# 08_-_Resolver.net
KiCad netlist of a schematic drawn in Altium Designer
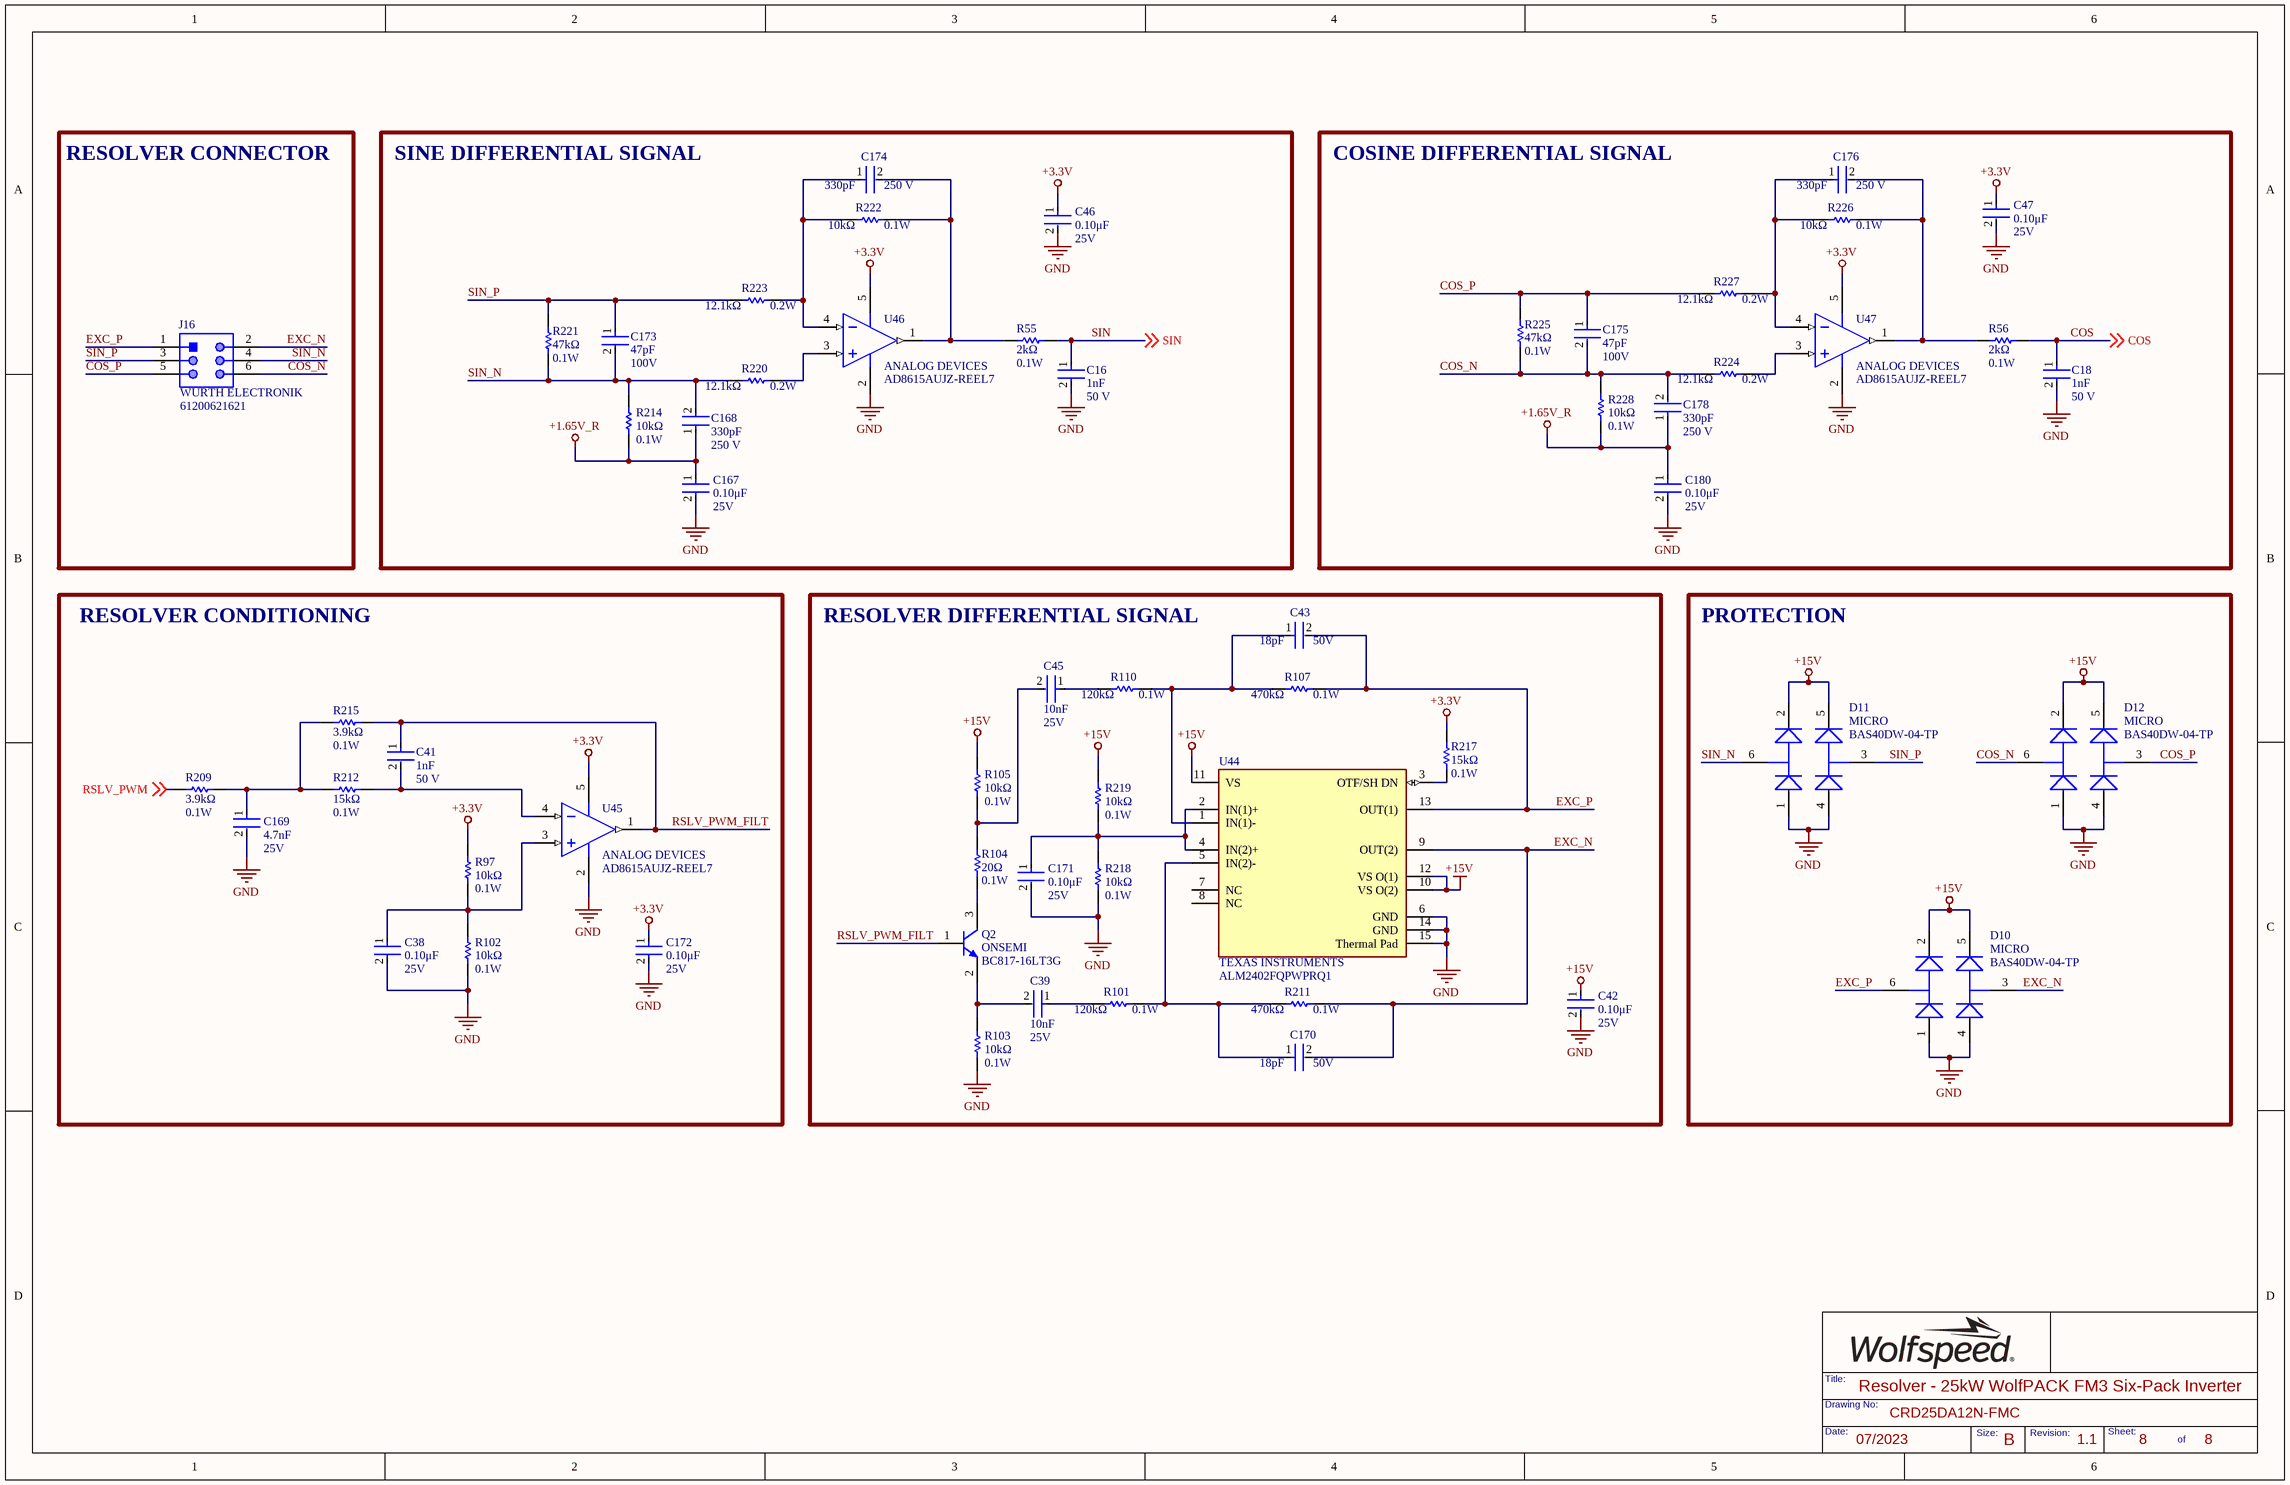
[diagram p0: 08 - Resolver.SchDoc]

(export (version "E")
  (design (tool "Eeschema 10.0.6"))
  (components
    (comp (ref "C16")
      (value "C0603C102K5RACAUTO")
      (footprint "FP-C0603C-CF-IPC_B")
      (description "CAP CER 1000PF 50V X7R 0603")
      (fields
        (field (name "CAPACITANCE") "1nF")
        (field (name "TOLERANCE") "0.1")
        (field (name "VOLTAGE RATING") "50 V")
        (field (name "OCTOPART") "https://octopart.com/c0603c102k5racauto-kemet-18822673")
      )
      (libsource (lib "Altium Content Vault") (part "b4654b650e69147ec39a6b967a45e02"))
    )
    (comp (ref "C18")
      (value "C0603C102K5RACAUTO")
      (footprint "FP-C0603C-CF-IPC_B")
      (description "CAP CER 1000PF 50V X7R 0603")
      (fields
        (field (name "CAPACITANCE") "1nF")
        (field (name "TOLERANCE") "0.1")
        (field (name "VOLTAGE RATING") "50 V")
        (field (name "OCTOPART") "https://octopart.com/c0603c102k5racauto-kemet-18822673")
      )
      (libsource (lib "Altium Content Vault") (part "b4654b650e69147ec39a6b967a45e02"))
    )
    (comp (ref "C38")
      (value "C0603C104K3RACTU")
      (footprint "FP-C0603C-CF-IPC_B")
      (description "CAP CER 0.1UF 25V X7R 0603")
      (fields
        (field (name "VOLTAGE RATING") "25V")
        (field (name "OCTOPART") "https://octopart.com/c0603c104k3ractu-kemet-127541")
        (field (name "MANUFACTURER") "KEMET")
        (field (name "CAPACITANCE") "0.10μF")
      )
      (libsource (lib "Altium Content Vault") (part "b4654b650e69147ec39a6b967a45e02"))
    )
    (comp (ref "C39")
      (value "10nF")
      (footprint "FP-C0603C-CF-IPC_B")
      (description "CAP CER 10000PF 25V X7R 0603")
      (fields
        (field (name "MANUFACTURER") "SAMSUNG")
        (field (name "MANUFACTURER PART NUMBER") "CL10B103KA8WPNC")
        (field (name "VOLTAGE RATING") "25V")
      )
      (libsource (lib "Inverter_25kW") (part "CL10B103KA8WPNC"))
    )
    (comp (ref "C41")
      (value "C0603C102K5RACAUTO")
      (footprint "FP-C0603C-CF-IPC_B")
      (description "CAP CER 1000PF 50V X7R 0603")
      (fields
        (field (name "CAPACITANCE") "1nF")
        (field (name "TOLERANCE") "0.1")
        (field (name "VOLTAGE RATING") "50 V")
        (field (name "OCTOPART") "https://octopart.com/c0603c102k5racauto-kemet-18822673")
      )
      (libsource (lib "Altium Content Vault") (part "b4654b650e69147ec39a6b967a45e02"))
    )
    (comp (ref "C42")
      (value "C0603C104K3RACTU")
      (footprint "FP-C0603C-CF-IPC_B")
      (description "CAP CER 0.1UF 25V X7R 0603")
      (fields
        (field (name "VOLTAGE RATING") "25V")
        (field (name "OCTOPART") "https://octopart.com/c0603c104k3ractu-kemet-127541")
        (field (name "MANUFACTURER") "KEMET")
        (field (name "CAPACITANCE") "0.10μF")
      )
      (libsource (lib "Altium Content Vault") (part "b4654b650e69147ec39a6b967a45e02"))
    )
    (comp (ref "C43")
      (value "06035A180JAT2A")
      (footprint "FP-C0603C-CF-IPC_B")
      (description "CAP CER 18PF 50V C0G/NP0 0603")
      (fields
        (field (name "MANUFACTURER") "KYOCERA AVX")
        (field (name "TOLERANCE") "5%")
        (field (name "CAPACITANCE") "18pF")
        (field (name "VOLTAGE RATING") "50V")
      )
      (libsource (lib "Inverter_25kW") (part "06035A180JAT2A"))
    )
    (comp (ref "C45")
      (value "10nF")
      (footprint "FP-C0603C-CF-IPC_B")
      (description "CAP CER 10000PF 25V X7R 0603")
      (fields
        (field (name "MANUFACTURER") "SAMSUNG")
        (field (name "MANUFACTURER PART NUMBER") "CL10B103KA8WPNC")
        (field (name "VOLTAGE RATING") "25V")
      )
      (libsource (lib "Inverter_25kW") (part "CL10B103KA8WPNC"))
    )
    (comp (ref "C46")
      (value "C0603C104K3RACTU")
      (footprint "FP-C0603C-CF-IPC_B")
      (description "CAP CER 0.1UF 25V X7R 0603")
      (fields
        (field (name "VOLTAGE RATING") "25V")
        (field (name "OCTOPART") "https://octopart.com/c0603c104k3ractu-kemet-127541")
        (field (name "MANUFACTURER") "KEMET")
        (field (name "CAPACITANCE") "0.10μF")
      )
      (libsource (lib "Altium Content Vault") (part "b4654b650e69147ec39a6b967a45e02"))
    )
    (comp (ref "C47")
      (value "C0603C104K3RACTU")
      (footprint "FP-C0603C-CF-IPC_B")
      (description "CAP CER 0.1UF 25V X7R 0603")
      (fields
        (field (name "VOLTAGE RATING") "25V")
        (field (name "OCTOPART") "https://octopart.com/c0603c104k3ractu-kemet-127541")
        (field (name "MANUFACTURER") "KEMET")
        (field (name "CAPACITANCE") "0.10μF")
      )
      (libsource (lib "Altium Content Vault") (part "b4654b650e69147ec39a6b967a45e02"))
    )
    (comp (ref "C167")
      (value "C0603C104K3RACTU")
      (footprint "FP-C0603C-CF-IPC_B")
      (description "CAP CER 0.1UF 25V X7R 0603")
      (fields
        (field (name "VOLTAGE RATING") "25V")
        (field (name "OCTOPART") "https://octopart.com/c0603c104k3ractu-kemet-127541")
        (field (name "MANUFACTURER") "KEMET")
        (field (name "CAPACITANCE") "0.10μF")
      )
      (libsource (lib "Altium Content Vault") (part "b4654b650e69147ec39a6b967a45e02"))
    )
    (comp (ref "C168")
      (value "330pF")
      (footprint "FP-C0603C-CF-IPC_B")
      (description "CAP CER 330PF 250V C0G/NP0 0603")
      (fields
        (field (name "OCTOPART") "https://octopart.com/c0603c331jagac7867-kemet-83501965")
        (field (name "MANUFACTURER PART NUMBER") "C0603C331JAGAC7867")
        (field (name "VOLTAGE RATING") "250 V")
      )
      (libsource (lib "Altium Content Vault") (part "b4654b650e69147ec39a6b967a45e02"))
    )
    (comp (ref "C169")
      (value "C0603C472K3RAC7867")
      (footprint "FP-C0603C-CF-IPC_B")
      (description "CAP CER 4700PF 25V 10% X7R 0603")
      (fields
        (field (name "MANUFACTURER") "KEMET")
        (field (name "MANUFACTURER PART NUMBER") "C0603C472K3RACTU")
        (field (name "VOLTAGE RATING") "25V")
        (field (name "CAPACITANCE") "4.7nF")
      )
      (libsource (lib "Inverter_25kW") (part "C0603C472K3RAC7867"))
    )
    (comp (ref "C170")
      (value "06035A180JAT2A")
      (footprint "FP-C0603C-CF-IPC_B")
      (description "CAP CER 18PF 50V C0G/NP0 0603")
      (fields
        (field (name "MANUFACTURER") "KYOCERA AVX")
        (field (name "TOLERANCE") "5%")
        (field (name "CAPACITANCE") "18pF")
        (field (name "VOLTAGE RATING") "50V")
      )
      (libsource (lib "Inverter_25kW") (part "06035A180JAT2A"))
    )
    (comp (ref "C171")
      (value "C0603C104K3RACTU")
      (footprint "FP-C0603C-CF-IPC_B")
      (description "CAP CER 0.1UF 25V X7R 0603")
      (fields
        (field (name "VOLTAGE RATING") "25V")
        (field (name "OCTOPART") "https://octopart.com/c0603c104k3ractu-kemet-127541")
        (field (name "MANUFACTURER") "KEMET")
        (field (name "CAPACITANCE") "0.10μF")
      )
      (libsource (lib "Altium Content Vault") (part "b4654b650e69147ec39a6b967a45e02"))
    )
    (comp (ref "C172")
      (value "C0603C104K3RACTU")
      (footprint "FP-C0603C-CF-IPC_B")
      (description "CAP CER 0.1UF 25V X7R 0603")
      (fields
        (field (name "VOLTAGE RATING") "25V")
        (field (name "OCTOPART") "https://octopart.com/c0603c104k3ractu-kemet-127541")
        (field (name "MANUFACTURER") "KEMET")
        (field (name "CAPACITANCE") "0.10μF")
      )
      (libsource (lib "Altium Content Vault") (part "b4654b650e69147ec39a6b967a45e02"))
    )
    (comp (ref "C173")
      (value "C0603C470J1GACTU")
      (footprint "FP-C0603C-CF-IPC_B")
      (description "CAP CER 47PF 100V C0G/NP0 0603")
      (fields
        (field (name "MANUFACTURER") "KEMET")
        (field (name "TOLERANCE") "5%")
        (field (name "CAPACITANCE") "47pF")
        (field (name "VOLTAGE RATING (DC)") "100V")
      )
      (libsource (lib "Inverter_25kW") (part "C0603C470J1GACTU"))
    )
    (comp (ref "C174")
      (value "330pF")
      (footprint "FP-C0603C-CF-IPC_B")
      (description "CAP CER 330PF 250V C0G/NP0 0603")
      (fields
        (field (name "OCTOPART") "https://octopart.com/c0603c331jagac7867-kemet-83501965")
        (field (name "MANUFACTURER PART NUMBER") "C0603C331JAGAC7867")
        (field (name "VOLTAGE RATING") "250 V")
      )
      (libsource (lib "Altium Content Vault") (part "b4654b650e69147ec39a6b967a45e02"))
    )
    (comp (ref "C175")
      (value "C0603C470J1GACTU")
      (footprint "FP-C0603C-CF-IPC_B")
      (description "CAP CER 47PF 100V C0G/NP0 0603")
      (fields
        (field (name "MANUFACTURER") "KEMET")
        (field (name "TOLERANCE") "5%")
        (field (name "CAPACITANCE") "47pF")
        (field (name "VOLTAGE RATING (DC)") "100V")
      )
      (libsource (lib "Inverter_25kW") (part "C0603C470J1GACTU"))
    )
    (comp (ref "C176")
      (value "330pF")
      (footprint "FP-C0603C-CF-IPC_B")
      (description "CAP CER 330PF 250V C0G/NP0 0603")
      (fields
        (field (name "OCTOPART") "https://octopart.com/c0603c331jagac7867-kemet-83501965")
        (field (name "MANUFACTURER PART NUMBER") "C0603C331JAGAC7867")
        (field (name "VOLTAGE RATING") "250 V")
      )
      (libsource (lib "Altium Content Vault") (part "b4654b650e69147ec39a6b967a45e02"))
    )
    (comp (ref "C178")
      (value "330pF")
      (footprint "FP-C0603C-CF-IPC_B")
      (description "CAP CER 330PF 250V C0G/NP0 0603")
      (fields
        (field (name "OCTOPART") "https://octopart.com/c0603c331jagac7867-kemet-83501965")
        (field (name "MANUFACTURER PART NUMBER") "C0603C331JAGAC7867")
        (field (name "VOLTAGE RATING") "250 V")
      )
      (libsource (lib "Altium Content Vault") (part "b4654b650e69147ec39a6b967a45e02"))
    )
    (comp (ref "C180")
      (value "C0603C104K3RACTU")
      (footprint "FP-C0603C-CF-IPC_B")
      (description "CAP CER 0.1UF 25V X7R 0603")
      (fields
        (field (name "VOLTAGE RATING") "25V")
        (field (name "OCTOPART") "https://octopart.com/c0603c104k3ractu-kemet-127541")
        (field (name "MANUFACTURER") "KEMET")
        (field (name "CAPACITANCE") "0.10μF")
      )
      (libsource (lib "Altium Content Vault") (part "b4654b650e69147ec39a6b967a45e02"))
    )
    (comp (ref "D10")
      (value "BAS40DW-04-TP")
      (footprint "SOT65P222X120-6N")
      (description "DIODE ARRAY SCHOTTKY 40V SOT363")
      (fields
        (field (name "MANUFACTURER") "MICRO COMMERCIAL")
        (field (name "MANUFACTURER PRINT") "MICRO")
        (field (name "MANUFACTURER PART NUMBER") "BAS40DW-04-TP")
      )
      (libsource (lib "Inverter_25kW") (part "BAS40DW-04-TP"))
    )
    (comp (ref "D11")
      (value "BAS40DW-04-TP")
      (footprint "SOT65P222X120-6N")
      (description "DIODE ARRAY SCHOTTKY 40V SOT363")
      (fields
        (field (name "MANUFACTURER") "MICRO COMMERCIAL")
        (field (name "MANUFACTURER PRINT") "MICRO")
        (field (name "MANUFACTURER PART NUMBER") "BAS40DW-04-TP")
      )
      (libsource (lib "Inverter_25kW") (part "BAS40DW-04-TP"))
    )
    (comp (ref "D12")
      (value "BAS40DW-04-TP")
      (footprint "SOT65P222X120-6N")
      (description "DIODE ARRAY SCHOTTKY 40V SOT363")
      (fields
        (field (name "MANUFACTURER") "MICRO COMMERCIAL")
        (field (name "MANUFACTURER PRINT") "MICRO")
        (field (name "MANUFACTURER PART NUMBER") "BAS40DW-04-TP")
      )
      (libsource (lib "Inverter_25kW") (part "BAS40DW-04-TP"))
    )
    (comp (ref "J16")
      (value "61200621621")
      (footprint "61200621621")
      (description "CONN HEADER VERT 6POS 2.54MM")
      (fields
        (field (name "MANUFACTURER PART NUMBER") "61200621621")
        (field (name "MANUFACTURER") "WURTH ELECTRONIK")
        (field (name "PUBLISHER") "WurthElektronik")
      )
      (libsource (lib "Altium Content Vault") (part "WE-CN-2P-M-R6"))
    )
    (comp (ref "Q2")
      (value "BC817-16LT3G")
      (footprint "ONSC-SOT-23-3-318-08_V")
      (description "TRANS NPN 45V 0.5A SOT23-3")
      (fields (field (name "MANUFACTURER") "ONSEMI") (field (name "MANUFACTURER PART NUMBER") "BC817-16LT3G"))
      (libsource (lib "Altium Content Vault") (part "ONSC-NPN-B1E2C3-3"))
    )
    (comp (ref "R55")
      (value "RT0603DRE072KL")
      (footprint "FP-MCR03-IPC_B")
      (description "RES SMD 2K OHM 0.5% 1/10W 0603")
      (fields
        (field (name "MANUFACTURER") "YAGEO")
        (field (name "TOLERANCE") "0.5%")
        (field (name "RESISTANCE") "2kΩ")
        (field (name "POWER RATING") "0.1W")
      )
      (libsource (lib "Inverter_25kW") (part "RT0603DRE072KL"))
    )
    (comp (ref "R56")
      (value "RT0603DRE072KL")
      (footprint "FP-MCR03-IPC_B")
      (description "RES SMD 2K OHM 0.5% 1/10W 0603")
      (fields
        (field (name "MANUFACTURER") "YAGEO")
        (field (name "TOLERANCE") "0.5%")
        (field (name "RESISTANCE") "2kΩ")
        (field (name "POWER RATING") "0.1W")
      )
      (libsource (lib "Inverter_25kW") (part "RT0603DRE072KL"))
    )
    (comp (ref "R97")
      (value "ERJ3EKF1002V")
      (footprint "FP-MCR03-IPC_B")
      (description "RES SMD 10K OHM 1% 1/10W 0603")
      (fields
        (field (name "MANUFACTURER") "PANASONIC")
        (field (name "MANUFACTURER PART NUMBER") "ERJ-3EKF1002V")
        (field (name "RESISTANCE") "10kΩ")
        (field (name "MAX POWER DISSIPATION") "0.1W")
      )
      (libsource (lib "Inverter_25kW") (part "ERJ3EKF1002V"))
    )
    (comp (ref "R101")
      (value "RC0603FR-07120KL")
      (footprint "FP-MCR03-IPC_B")
      (description "RES 120K OHM 1% 1/10W 0603")
      (fields
        (field (name "MANUFACTURER") "YAGEO")
        (field (name "TOLERANCE") "1%")
        (field (name "MAX POWER DISSIPATION") "0.1W")
        (field (name "RESISTANCE") "120kΩ")
      )
      (libsource (lib "Inverter_25kW") (part "RC0603FR-07120KL"))
    )
    (comp (ref "R102")
      (value "ERJ3EKF1002V")
      (footprint "FP-MCR03-IPC_B")
      (description "RES SMD 10K OHM 1% 1/10W 0603")
      (fields
        (field (name "MANUFACTURER") "PANASONIC")
        (field (name "MANUFACTURER PART NUMBER") "ERJ-3EKF1002V")
        (field (name "RESISTANCE") "10kΩ")
        (field (name "MAX POWER DISSIPATION") "0.1W")
      )
      (libsource (lib "Inverter_25kW") (part "ERJ3EKF1002V"))
    )
    (comp (ref "R103")
      (value "ERJ3EKF1002V")
      (footprint "FP-MCR03-IPC_B")
      (description "RES SMD 10K OHM 1% 1/10W 0603")
      (fields
        (field (name "MANUFACTURER") "PANASONIC")
        (field (name "MANUFACTURER PART NUMBER") "ERJ-3EKF1002V")
        (field (name "RESISTANCE") "10kΩ")
        (field (name "MAX POWER DISSIPATION") "0.1W")
      )
      (libsource (lib "Inverter_25kW") (part "ERJ3EKF1002V"))
    )
    (comp (ref "R104")
      (value "RC0603JR-0720RL")
      (footprint "FP-MCR03-IPC_B")
      (description "RES 20 OHM 5% 1/10W 0603")
      (fields
        (field (name "MANUFACTURER") "YAGEO")
        (field (name "TOLERANCE") "5%")
        (field (name "RESISTANCE") "20Ω")
        (field (name "POWER RATING") "0.1W")
      )
      (libsource (lib "Inverter_25kW") (part "RC0603JR-0720RL"))
    )
    (comp (ref "R105")
      (value "ERJ3EKF1002V")
      (footprint "FP-MCR03-IPC_B")
      (description "RES SMD 10K OHM 1% 1/10W 0603")
      (fields
        (field (name "MANUFACTURER") "PANASONIC")
        (field (name "MANUFACTURER PART NUMBER") "ERJ-3EKF1002V")
        (field (name "RESISTANCE") "10kΩ")
        (field (name "MAX POWER DISSIPATION") "0.1W")
      )
      (libsource (lib "Inverter_25kW") (part "ERJ3EKF1002V"))
    )
    (comp (ref "R107")
      (value "RC0603FR-07470KL")
      (footprint "FP-MCR03-IPC_B")
      (description "RES 470K OHM 1% 1/10W 0603")
      (fields
        (field (name "MANUFACTURER") "YAGEO")
        (field (name "TOLERANCE") "1%")
        (field (name "RESISTANCE") "470kΩ")
        (field (name "POWER RATING") "0.1W")
      )
      (libsource (lib "Inverter_25kW") (part "RC0603FR-07470KL"))
    )
    (comp (ref "R110")
      (value "RC0603FR-07120KL")
      (footprint "FP-MCR03-IPC_B")
      (description "RES 120K OHM 1% 1/10W 0603")
      (fields
        (field (name "MANUFACTURER") "YAGEO")
        (field (name "TOLERANCE") "1%")
        (field (name "MAX POWER DISSIPATION") "0.1W")
        (field (name "RESISTANCE") "120kΩ")
      )
      (libsource (lib "Inverter_25kW") (part "RC0603FR-07120KL"))
    )
    (comp (ref "R209")
      (value "ERJ3EKF3901V")
      (footprint "FP-MCR03-IPC_B")
      (description "RES SMD 3.9K OHM 1% 1/10W 0603")
      (fields
        (field (name "MANUFACTURER") "PANASONIC")
        (field (name "MANUFACTURER PART NUMBER") "ERJ-3EKF3901V")
        (field (name "RESISTANCE") "3.9kΩ")
        (field (name "POWER RATING") "0.1W")
      )
      (libsource (lib "Inverter_25kW") (part "ERJ3EKF3901V"))
    )
    (comp (ref "R211")
      (value "RC0603FR-07470KL")
      (footprint "FP-MCR03-IPC_B")
      (description "RES 470K OHM 1% 1/10W 0603")
      (fields
        (field (name "MANUFACTURER") "YAGEO")
        (field (name "TOLERANCE") "1%")
        (field (name "RESISTANCE") "470kΩ")
        (field (name "POWER RATING") "0.1W")
      )
      (libsource (lib "Inverter_25kW") (part "RC0603FR-07470KL"))
    )
    (comp (ref "R212")
      (value "ERA-3AED153V")
      (footprint "FP-MCR03-IPC_B")
      (description "RES SMD 15K OHM 0.5% 1/10W 0603")
      (fields
        (field (name "MANUFACTURER") "PANASONIC")
        (field (name "TOLERANCE") "0.5%")
        (field (name "RESISTANCE") "15kΩ")
        (field (name "POWER RATING") "0.1W")
      )
      (libsource (lib "Inverter_25kW") (part "ERA-3AED153V"))
    )
    (comp (ref "R214")
      (value "ERJ3EKF1002V")
      (footprint "FP-MCR03-IPC_B")
      (description "RES SMD 10K OHM 1% 1/10W 0603")
      (fields
        (field (name "MANUFACTURER") "PANASONIC")
        (field (name "MANUFACTURER PART NUMBER") "ERJ-3EKF1002V")
        (field (name "RESISTANCE") "10kΩ")
        (field (name "MAX POWER DISSIPATION") "0.1W")
      )
      (libsource (lib "Inverter_25kW") (part "ERJ3EKF1002V"))
    )
    (comp (ref "R215")
      (value "ERJ3EKF3901V")
      (footprint "FP-MCR03-IPC_B")
      (description "RES SMD 3.9K OHM 1% 1/10W 0603")
      (fields
        (field (name "MANUFACTURER") "PANASONIC")
        (field (name "MANUFACTURER PART NUMBER") "ERJ-3EKF3901V")
        (field (name "RESISTANCE") "3.9kΩ")
        (field (name "POWER RATING") "0.1W")
      )
      (libsource (lib "Inverter_25kW") (part "ERJ3EKF3901V"))
    )
    (comp (ref "R217")
      (value "ERA-3AED153V")
      (footprint "FP-MCR03-IPC_B")
      (description "RES SMD 15K OHM 0.5% 1/10W 0603")
      (fields
        (field (name "MANUFACTURER") "PANASONIC")
        (field (name "TOLERANCE") "0.5%")
        (field (name "RESISTANCE") "15kΩ")
        (field (name "POWER RATING") "0.1W")
      )
      (libsource (lib "Inverter_25kW") (part "ERA-3AED153V"))
    )
    (comp (ref "R218")
      (value "ERJ3EKF1002V")
      (footprint "FP-MCR03-IPC_B")
      (description "RES SMD 10K OHM 1% 1/10W 0603")
      (fields
        (field (name "MANUFACTURER") "PANASONIC")
        (field (name "MANUFACTURER PART NUMBER") "ERJ-3EKF1002V")
        (field (name "RESISTANCE") "10kΩ")
        (field (name "MAX POWER DISSIPATION") "0.1W")
      )
      (libsource (lib "Inverter_25kW") (part "ERJ3EKF1002V"))
    )
    (comp (ref "R219")
      (value "ERJ3EKF1002V")
      (footprint "FP-MCR03-IPC_B")
      (description "RES SMD 10K OHM 1% 1/10W 0603")
      (fields
        (field (name "MANUFACTURER") "PANASONIC")
        (field (name "MANUFACTURER PART NUMBER") "ERJ-3EKF1002V")
        (field (name "RESISTANCE") "10kΩ")
        (field (name "MAX POWER DISSIPATION") "0.1W")
      )
      (libsource (lib "Inverter_25kW") (part "ERJ3EKF1002V"))
    )
    (comp (ref "R220")
      (value "ERJ-PB3B1212V")
      (footprint "FP-MCR03-IPC_B")
      (description "RES SMD 12.1K OHM 0.1% 1/5W 0603")
      (fields
        (field (name "MANUFACTURER") "PANASONIC")
        (field (name "TOLERANCE") "0.1%")
        (field (name "RESISTANCE") "12.1kΩ")
        (field (name "MAX POWER DISSIPATION") "0.2W")
      )
      (libsource (lib "Inverter_25kW") (part "ERJ-PB3B1212V"))
    )
    (comp (ref "R221")
      (value "RC0603FR-0747KL")
      (footprint "FP-MCR03-IPC_B")
      (description "RES 47K OHM 1% 1/10W 0603")
      (fields
        (field (name "MANUFACTURER") "YAGEO")
        (field (name "TOLERANCE") "1%")
        (field (name "RESISTANCE") "47kΩ")
        (field (name "POWER RATING") "0.1W")
      )
      (libsource (lib "Inverter_25kW") (part "RC0603FR-0747KL"))
    )
    (comp (ref "R222")
      (value "ERJ3EKF1002V")
      (footprint "FP-MCR03-IPC_B")
      (description "RES SMD 10K OHM 1% 1/10W 0603")
      (fields
        (field (name "MANUFACTURER") "PANASONIC")
        (field (name "MANUFACTURER PART NUMBER") "ERJ-3EKF1002V")
        (field (name "RESISTANCE") "10kΩ")
        (field (name "MAX POWER DISSIPATION") "0.1W")
      )
      (libsource (lib "Inverter_25kW") (part "ERJ3EKF1002V"))
    )
    (comp (ref "R223")
      (value "ERJ-PB3B1212V")
      (footprint "FP-MCR03-IPC_B")
      (description "RES SMD 12.1K OHM 0.1% 1/5W 0603")
      (fields
        (field (name "MANUFACTURER") "PANASONIC")
        (field (name "TOLERANCE") "0.1%")
        (field (name "RESISTANCE") "12.1kΩ")
        (field (name "MAX POWER DISSIPATION") "0.2W")
      )
      (libsource (lib "Inverter_25kW") (part "ERJ-PB3B1212V"))
    )
    (comp (ref "R224")
      (value "ERJ-PB3B1212V")
      (footprint "FP-MCR03-IPC_B")
      (description "RES SMD 12.1K OHM 0.1% 1/5W 0603")
      (fields
        (field (name "MANUFACTURER") "PANASONIC")
        (field (name "TOLERANCE") "0.1%")
        (field (name "RESISTANCE") "12.1kΩ")
        (field (name "MAX POWER DISSIPATION") "0.2W")
      )
      (libsource (lib "Inverter_25kW") (part "ERJ-PB3B1212V"))
    )
    (comp (ref "R225")
      (value "RC0603FR-0747KL")
      (footprint "FP-MCR03-IPC_B")
      (description "RES 47K OHM 1% 1/10W 0603")
      (fields
        (field (name "MANUFACTURER") "YAGEO")
        (field (name "TOLERANCE") "1%")
        (field (name "RESISTANCE") "47kΩ")
        (field (name "POWER RATING") "0.1W")
      )
      (libsource (lib "Inverter_25kW") (part "RC0603FR-0747KL"))
    )
    (comp (ref "R226")
      (value "ERJ3EKF1002V")
      (footprint "FP-MCR03-IPC_B")
      (description "RES SMD 10K OHM 1% 1/10W 0603")
      (fields
        (field (name "MANUFACTURER") "PANASONIC")
        (field (name "MANUFACTURER PART NUMBER") "ERJ-3EKF1002V")
        (field (name "RESISTANCE") "10kΩ")
        (field (name "MAX POWER DISSIPATION") "0.1W")
      )
      (libsource (lib "Inverter_25kW") (part "ERJ3EKF1002V"))
    )
    (comp (ref "R227")
      (value "ERJ-PB3B1212V")
      (footprint "FP-MCR03-IPC_B")
      (description "RES SMD 12.1K OHM 0.1% 1/5W 0603")
      (fields
        (field (name "MANUFACTURER") "PANASONIC")
        (field (name "TOLERANCE") "0.1%")
        (field (name "RESISTANCE") "12.1kΩ")
        (field (name "MAX POWER DISSIPATION") "0.2W")
      )
      (libsource (lib "Inverter_25kW") (part "ERJ-PB3B1212V"))
    )
    (comp (ref "R228")
      (value "ERJ3EKF1002V")
      (footprint "FP-MCR03-IPC_B")
      (description "RES SMD 10K OHM 1% 1/10W 0603")
      (fields
        (field (name "MANUFACTURER") "PANASONIC")
        (field (name "MANUFACTURER PART NUMBER") "ERJ-3EKF1002V")
        (field (name "RESISTANCE") "10kΩ")
        (field (name "MAX POWER DISSIPATION") "0.1W")
      )
      (libsource (lib "Inverter_25kW") (part "ERJ3EKF1002V"))
    )
    (comp (ref "U44")
      (value "ALM2402FQPWPRQ1")
      (footprint "FP-PWP0014H-MFG")
      (description "IC POWER 2 CIRCUIT 14HTSSOP")
      (fields
        (field (name "MANUFACTURER PART NUMBER") "ALM2402FQPWPRQ1")
        (field (name "MANUFACTURER") "TEXAS INSTRUMENTS")
      )
      (libsource (lib "Inverter_25kW") (part "CMP-04895-000282-1"))
    )
    (comp (ref "U45")
      (value "AD8615AUJZ-REEL7")
      (footprint "ADI-UJ-5_M")
      (description "IC OPAMP GP 1 CIRCUIT TSOT23-5")
      (fields
        (field (name "MANUFACTURER") "ANALOG DEVICES")
        (field (name "GENERIC PART NUMBER") "AD8615")
        (field (name "MANUFACTURER PART NUMBER") "AD8615AUJZ-REEL7")
      )
      (libsource (lib "Altium Content Vault") (part "ADI-ADxxxx-X-5"))
    )
    (comp (ref "U46")
      (value "AD8615AUJZ-REEL7")
      (footprint "ADI-UJ-5_M")
      (description "IC OPAMP GP 1 CIRCUIT TSOT23-5")
      (fields
        (field (name "MANUFACTURER") "ANALOG DEVICES")
        (field (name "GENERIC PART NUMBER") "AD8615")
        (field (name "MANUFACTURER PART NUMBER") "AD8615AUJZ-REEL7")
      )
      (libsource (lib "Altium Content Vault") (part "ADI-ADxxxx-X-5"))
    )
    (comp (ref "U47")
      (value "AD8615AUJZ-REEL7")
      (footprint "ADI-UJ-5_M")
      (description "IC OPAMP GP 1 CIRCUIT TSOT23-5")
      (fields
        (field (name "MANUFACTURER") "ANALOG DEVICES")
        (field (name "GENERIC PART NUMBER") "AD8615")
        (field (name "MANUFACTURER PART NUMBER") "AD8615AUJZ-REEL7")
      )
      (libsource (lib "Altium Content Vault") (part "ADI-ADxxxx-X-5"))
    )
  )
  (nets
    (net (code "1") (name "+1.65V_R") (class "Default")
      (node (ref "C167") (pin "1") (pinfunction "1_1") (pintype "passive"))
      (node (ref "C168") (pin "1") (pinfunction "1_1") (pintype "passive"))
      (node (ref "C178") (pin "1") (pinfunction "1_1") (pintype "passive"))
      (node (ref "C180") (pin "1") (pinfunction "1_1") (pintype "passive"))
      (node (ref "R214") (pin "1") (pinfunction "1_1") (pintype "passive"))
      (node (ref "R228") (pin "1") (pinfunction "1_1") (pintype "passive"))
    )
    (net (code "2") (name "+3.3V") (class "Default")
      (node (ref "C172") (pin "1") (pinfunction "1_1") (pintype "passive"))
      (node (ref "C46") (pin "1") (pinfunction "1_1") (pintype "passive"))
      (node (ref "C47") (pin "1") (pinfunction "1_1") (pintype "passive"))
      (node (ref "R217") (pin "2") (pinfunction "2_2") (pintype "passive"))
      (node (ref "R97") (pin "2") (pinfunction "2_2") (pintype "passive"))
      (node (ref "U45") (pin "5") (pinfunction "+V_5") (pintype "power_in"))
      (node (ref "U46") (pin "5") (pinfunction "+V_5") (pintype "power_in"))
      (node (ref "U47") (pin "5") (pinfunction "+V_5") (pintype "power_in"))
    )
    (net (code "3") (name "+15V") (class "Default")
      (node (ref "C42") (pin "1") (pinfunction "1_1") (pintype "passive"))
      (node (ref "D10") (pin "2") (pinfunction "C1_2") (pintype "passive"))
      (node (ref "D10") (pin "5") (pinfunction "C2_5") (pintype "passive"))
      (node (ref "D11") (pin "2") (pinfunction "C1_2") (pintype "passive"))
      (node (ref "D11") (pin "5") (pinfunction "C2_5") (pintype "passive"))
      (node (ref "D12") (pin "2") (pinfunction "C1_2") (pintype "passive"))
      (node (ref "D12") (pin "5") (pinfunction "C2_5") (pintype "passive"))
      (node (ref "R105") (pin "2") (pinfunction "2_2") (pintype "passive"))
      (node (ref "R219") (pin "2") (pinfunction "2_2") (pintype "passive"))
      (node (ref "U44") (pin "10") (pinfunction "VS_O(2)_10") (pintype "power_in"))
      (node (ref "U44") (pin "11") (pinfunction "VS_11") (pintype "power_in"))
      (node (ref "U44") (pin "12") (pinfunction "VS_O(1)_12") (pintype "power_in"))
    )
    (net (code "4") (name "/COS_N") (class "Default")
      (node (ref "C175") (pin "2") (pinfunction "2_2") (pintype "passive"))
      (node (ref "C178") (pin "2") (pinfunction "2_2") (pintype "passive"))
      (node (ref "D12") (pin "6") (pinfunction "AC1_6") (pintype "passive"))
      (node (ref "J16") (pin "6") (pinfunction "6_6") (pintype "passive"))
      (node (ref "R224") (pin "1") (pinfunction "1_1") (pintype "passive"))
      (node (ref "R225") (pin "1") (pinfunction "1_1") (pintype "passive"))
      (node (ref "R228") (pin "2") (pinfunction "2_2") (pintype "passive"))
    )
    (net (code "5") (name "/COS_P") (class "Default")
      (node (ref "C175") (pin "1") (pinfunction "1_1") (pintype "passive"))
      (node (ref "D12") (pin "3") (pinfunction "AC2_3") (pintype "passive"))
      (node (ref "J16") (pin "5") (pinfunction "5_5") (pintype "passive"))
      (node (ref "R225") (pin "2") (pinfunction "2_2") (pintype "passive"))
      (node (ref "R227") (pin "1") (pinfunction "1_1") (pintype "passive"))
    )
    (net (code "6") (name "/EXC_N") (class "Default")
      (node (ref "C170") (pin "2") (pinfunction "2_2") (pintype "passive"))
      (node (ref "D10") (pin "3") (pinfunction "AC2_3") (pintype "passive"))
      (node (ref "J16") (pin "2") (pinfunction "2_2") (pintype "passive"))
      (node (ref "R211") (pin "2") (pinfunction "2_2") (pintype "passive"))
      (node (ref "U44") (pin "9") (pinfunction "OUT(2)_9") (pintype "passive"))
    )
    (net (code "7") (name "/EXC_P") (class "Default")
      (node (ref "C43") (pin "2") (pinfunction "2_2") (pintype "passive"))
      (node (ref "D10") (pin "6") (pinfunction "AC1_6") (pintype "passive"))
      (node (ref "J16") (pin "1") (pinfunction "1_1") (pintype "passive"))
      (node (ref "R107") (pin "2") (pinfunction "2_2") (pintype "passive"))
      (node (ref "U44") (pin "13") (pinfunction "OUT(1)_13") (pintype "passive"))
    )
    (net (code "8") (name "/RSLV_PWM_FILT") (class "Default")
      (node (ref "C41") (pin "1") (pinfunction "1_1") (pintype "passive"))
      (node (ref "Q2") (pin "1") (pinfunction "B_1") (pintype "passive"))
      (node (ref "R215") (pin "2") (pinfunction "2_2") (pintype "passive"))
      (node (ref "U45") (pin "1") (pinfunction "OUT_1") (pintype "output"))
    )
    (net (code "9") (name "/SIN_N") (class "Default")
      (node (ref "C168") (pin "2") (pinfunction "2_2") (pintype "passive"))
      (node (ref "C173") (pin "2") (pinfunction "2_2") (pintype "passive"))
      (node (ref "D11") (pin "6") (pinfunction "AC1_6") (pintype "passive"))
      (node (ref "J16") (pin "4") (pinfunction "4_4") (pintype "passive"))
      (node (ref "R214") (pin "2") (pinfunction "2_2") (pintype "passive"))
      (node (ref "R220") (pin "1") (pinfunction "1_1") (pintype "passive"))
      (node (ref "R221") (pin "1") (pinfunction "1_1") (pintype "passive"))
    )
    (net (code "10") (name "/SIN_P") (class "Default")
      (node (ref "C173") (pin "1") (pinfunction "1_1") (pintype "passive"))
      (node (ref "D11") (pin "3") (pinfunction "AC2_3") (pintype "passive"))
      (node (ref "J16") (pin "3") (pinfunction "3_3") (pintype "passive"))
      (node (ref "R221") (pin "2") (pinfunction "2_2") (pintype "passive"))
      (node (ref "R223") (pin "1") (pinfunction "1_1") (pintype "passive"))
    )
    (net (code "11") (name "COS") (class "Default")
      (node (ref "C18") (pin "1") (pinfunction "1_1") (pintype "passive"))
      (node (ref "R56") (pin "2") (pinfunction "2_2") (pintype "passive"))
    )
    (net (code "12") (name "GND") (class "Default")
      (node (ref "C16") (pin "2") (pinfunction "2_2") (pintype "passive"))
      (node (ref "C167") (pin "2") (pinfunction "2_2") (pintype "passive"))
      (node (ref "C169") (pin "2") (pinfunction "2_2") (pintype "passive"))
      (node (ref "C171") (pin "2") (pinfunction "2_2") (pintype "passive"))
      (node (ref "C172") (pin "2") (pinfunction "2_2") (pintype "passive"))
      (node (ref "C18") (pin "2") (pinfunction "2_2") (pintype "passive"))
      (node (ref "C180") (pin "2") (pinfunction "2_2") (pintype "passive"))
      (node (ref "C38") (pin "2") (pinfunction "2_2") (pintype "passive"))
      (node (ref "C42") (pin "2") (pinfunction "2_2") (pintype "passive"))
      (node (ref "C46") (pin "2") (pinfunction "2_2") (pintype "passive"))
      (node (ref "C47") (pin "2") (pinfunction "2_2") (pintype "passive"))
      (node (ref "D10") (pin "1") (pinfunction "A1_1") (pintype "passive"))
      (node (ref "D10") (pin "4") (pinfunction "A2_4") (pintype "passive"))
      (node (ref "D11") (pin "1") (pinfunction "A1_1") (pintype "passive"))
      (node (ref "D11") (pin "4") (pinfunction "A2_4") (pintype "passive"))
      (node (ref "D12") (pin "1") (pinfunction "A1_1") (pintype "passive"))
      (node (ref "D12") (pin "4") (pinfunction "A2_4") (pintype "passive"))
      (node (ref "R102") (pin "1") (pinfunction "1_1") (pintype "passive"))
      (node (ref "R103") (pin "1") (pinfunction "1_1") (pintype "passive"))
      (node (ref "R218") (pin "1") (pinfunction "1_1") (pintype "passive"))
      (node (ref "U44") (pin "14") (pinfunction "GND_14") (pintype "power_in"))
      (node (ref "U44") (pin "15") (pinfunction "Thermal_Pad_15") (pintype "power_in"))
      (node (ref "U44") (pin "6") (pinfunction "GND_6") (pintype "power_in"))
      (node (ref "U45") (pin "2") (pinfunction "-V_2") (pintype "power_in"))
      (node (ref "U46") (pin "2") (pinfunction "-V_2") (pintype "power_in"))
      (node (ref "U47") (pin "2") (pinfunction "-V_2") (pintype "power_in"))
    )
    (net (code "13") (name "Net-(C39-Pad1)") (class "Default")
      (node (ref "C39") (pin "1") (pinfunction "1_1") (pintype "passive"))
      (node (ref "R101") (pin "1") (pinfunction "1_1") (pintype "passive"))
    )
    (net (code "14") (name "Net-(C45-Pad1)") (class "Default")
      (node (ref "C45") (pin "1") (pinfunction "1_1") (pintype "passive"))
      (node (ref "R110") (pin "1") (pinfunction "1_1") (pintype "passive"))
    )
    (net (code "15") (name "Net-(C45-Pad2)") (class "Default")
      (node (ref "C45") (pin "2") (pinfunction "2_2") (pintype "passive"))
      (node (ref "R104") (pin "2") (pinfunction "2_2") (pintype "passive"))
      (node (ref "R105") (pin "1") (pinfunction "1_1") (pintype "passive"))
    )
    (net (code "16") (name "Net-(C169-Pad1)") (class "Default")
      (node (ref "C169") (pin "1") (pinfunction "1_1") (pintype "passive"))
      (node (ref "R209") (pin "2") (pinfunction "2_2") (pintype "passive"))
      (node (ref "R212") (pin "2") (pinfunction "2_2") (pintype "passive"))
      (node (ref "R215") (pin "1") (pinfunction "1_1") (pintype "passive"))
    )
    (net (code "17") (name "Net-(Q2-C)") (class "Default")
      (node (ref "Q2") (pin "3") (pinfunction "C_3") (pintype "passive"))
      (node (ref "R104") (pin "1") (pinfunction "1_1") (pintype "passive"))
    )
    (net (code "18") (name "Net-(Q2-E)") (class "Default")
      (node (ref "C39") (pin "2") (pinfunction "2_2") (pintype "passive"))
      (node (ref "Q2") (pin "2") (pinfunction "E_2") (pintype "passive"))
      (node (ref "R103") (pin "2") (pinfunction "2_2") (pintype "passive"))
    )
    (net (code "19") (name "Net-(U44-IN(1)+)") (class "Default")
      (node (ref "C171") (pin "1") (pinfunction "1_1") (pintype "passive"))
      (node (ref "R218") (pin "2") (pinfunction "2_2") (pintype "passive"))
      (node (ref "R219") (pin "1") (pinfunction "1_1") (pintype "passive"))
      (node (ref "U44") (pin "2") (pinfunction "IN(1)+_2") (pintype "tri_state"))
      (node (ref "U44") (pin "4") (pinfunction "IN(2)+_4") (pintype "tri_state"))
    )
    (net (code "20") (name "Net-(U44-IN(1)-)") (class "Default")
      (node (ref "C43") (pin "1") (pinfunction "1_1") (pintype "passive"))
      (node (ref "R107") (pin "1") (pinfunction "1_1") (pintype "passive"))
      (node (ref "R110") (pin "2") (pinfunction "2_2") (pintype "passive"))
      (node (ref "U44") (pin "1") (pinfunction "IN(1)-_1") (pintype "tri_state"))
    )
    (net (code "21") (name "Net-(U44-IN(2)-)") (class "Default")
      (node (ref "C170") (pin "1") (pinfunction "1_1") (pintype "passive"))
      (node (ref "R101") (pin "2") (pinfunction "2_2") (pintype "passive"))
      (node (ref "R211") (pin "1") (pinfunction "1_1") (pintype "passive"))
      (node (ref "U44") (pin "5") (pinfunction "IN(2)-_5") (pintype "tri_state"))
    )
    (net (code "22") (name "Net-(U44-OTF{slash}SH_DN)") (class "Default")
      (node (ref "R217") (pin "1") (pinfunction "1_1") (pintype "passive"))
      (node (ref "U44") (pin "3") (pinfunction "OTF/SH_DN_3") (pintype "bidirectional"))
    )
    (net (code "23") (name "Net-(U45-+IN)") (class "Default")
      (node (ref "C38") (pin "1") (pinfunction "1_1") (pintype "passive"))
      (node (ref "R102") (pin "2") (pinfunction "2_2") (pintype "passive"))
      (node (ref "R97") (pin "1") (pinfunction "1_1") (pintype "passive"))
      (node (ref "U45") (pin "3") (pinfunction "+IN_3") (pintype "input"))
    )
    (net (code "24") (name "Net-(U45--IN)") (class "Default")
      (node (ref "C41") (pin "2") (pinfunction "2_2") (pintype "passive"))
      (node (ref "R212") (pin "1") (pinfunction "1_1") (pintype "passive"))
      (node (ref "U45") (pin "4") (pinfunction "-IN_4") (pintype "input"))
    )
    (net (code "25") (name "Net-(U46-+IN)") (class "Default")
      (node (ref "R220") (pin "2") (pinfunction "2_2") (pintype "passive"))
      (node (ref "U46") (pin "3") (pinfunction "+IN_3") (pintype "input"))
    )
    (net (code "26") (name "Net-(U46--IN)") (class "Default")
      (node (ref "C174") (pin "1") (pinfunction "1_1") (pintype "passive"))
      (node (ref "R222") (pin "2") (pinfunction "2_2") (pintype "passive"))
      (node (ref "R223") (pin "2") (pinfunction "2_2") (pintype "passive"))
      (node (ref "U46") (pin "4") (pinfunction "-IN_4") (pintype "input"))
    )
    (net (code "27") (name "Net-(U46-OUT)") (class "Default")
      (node (ref "C174") (pin "2") (pinfunction "2_2") (pintype "passive"))
      (node (ref "R222") (pin "1") (pinfunction "1_1") (pintype "passive"))
      (node (ref "R55") (pin "1") (pinfunction "1_1") (pintype "passive"))
      (node (ref "U46") (pin "1") (pinfunction "OUT_1") (pintype "output"))
    )
    (net (code "28") (name "Net-(U47-+IN)") (class "Default")
      (node (ref "R224") (pin "2") (pinfunction "2_2") (pintype "passive"))
      (node (ref "U47") (pin "3") (pinfunction "+IN_3") (pintype "input"))
    )
    (net (code "29") (name "Net-(U47--IN)") (class "Default")
      (node (ref "C176") (pin "1") (pinfunction "1_1") (pintype "passive"))
      (node (ref "R226") (pin "2") (pinfunction "2_2") (pintype "passive"))
      (node (ref "R227") (pin "2") (pinfunction "2_2") (pintype "passive"))
      (node (ref "U47") (pin "4") (pinfunction "-IN_4") (pintype "input"))
    )
    (net (code "30") (name "Net-(U47-OUT)") (class "Default")
      (node (ref "C176") (pin "2") (pinfunction "2_2") (pintype "passive"))
      (node (ref "R226") (pin "1") (pinfunction "1_1") (pintype "passive"))
      (node (ref "R56") (pin "1") (pinfunction "1_1") (pintype "passive"))
      (node (ref "U47") (pin "1") (pinfunction "OUT_1") (pintype "output"))
    )
    (net (code "31") (name "RSLV_PWM") (class "Default")
      (node (ref "R209") (pin "1") (pinfunction "1_1") (pintype "passive"))
    )
    (net (code "32") (name "SIN") (class "Default")
      (node (ref "C16") (pin "1") (pinfunction "1_1") (pintype "passive"))
      (node (ref "R55") (pin "2") (pinfunction "2_2") (pintype "passive"))
    )
    (net (code "33") (name "unconnected-(U44-NC-Pad7)") (class "Default")
      (node (ref "U44") (pin "7") (pinfunction "NC_7") (pintype "passive"))
    )
    (net (code "34") (name "unconnected-(U44-NC-Pad8)") (class "Default")
      (node (ref "U44") (pin "8") (pinfunction "NC_8") (pintype "passive"))
    )
  )
)
